# untitled.net
KiCad netlist of a schematic drawn in EAGLE
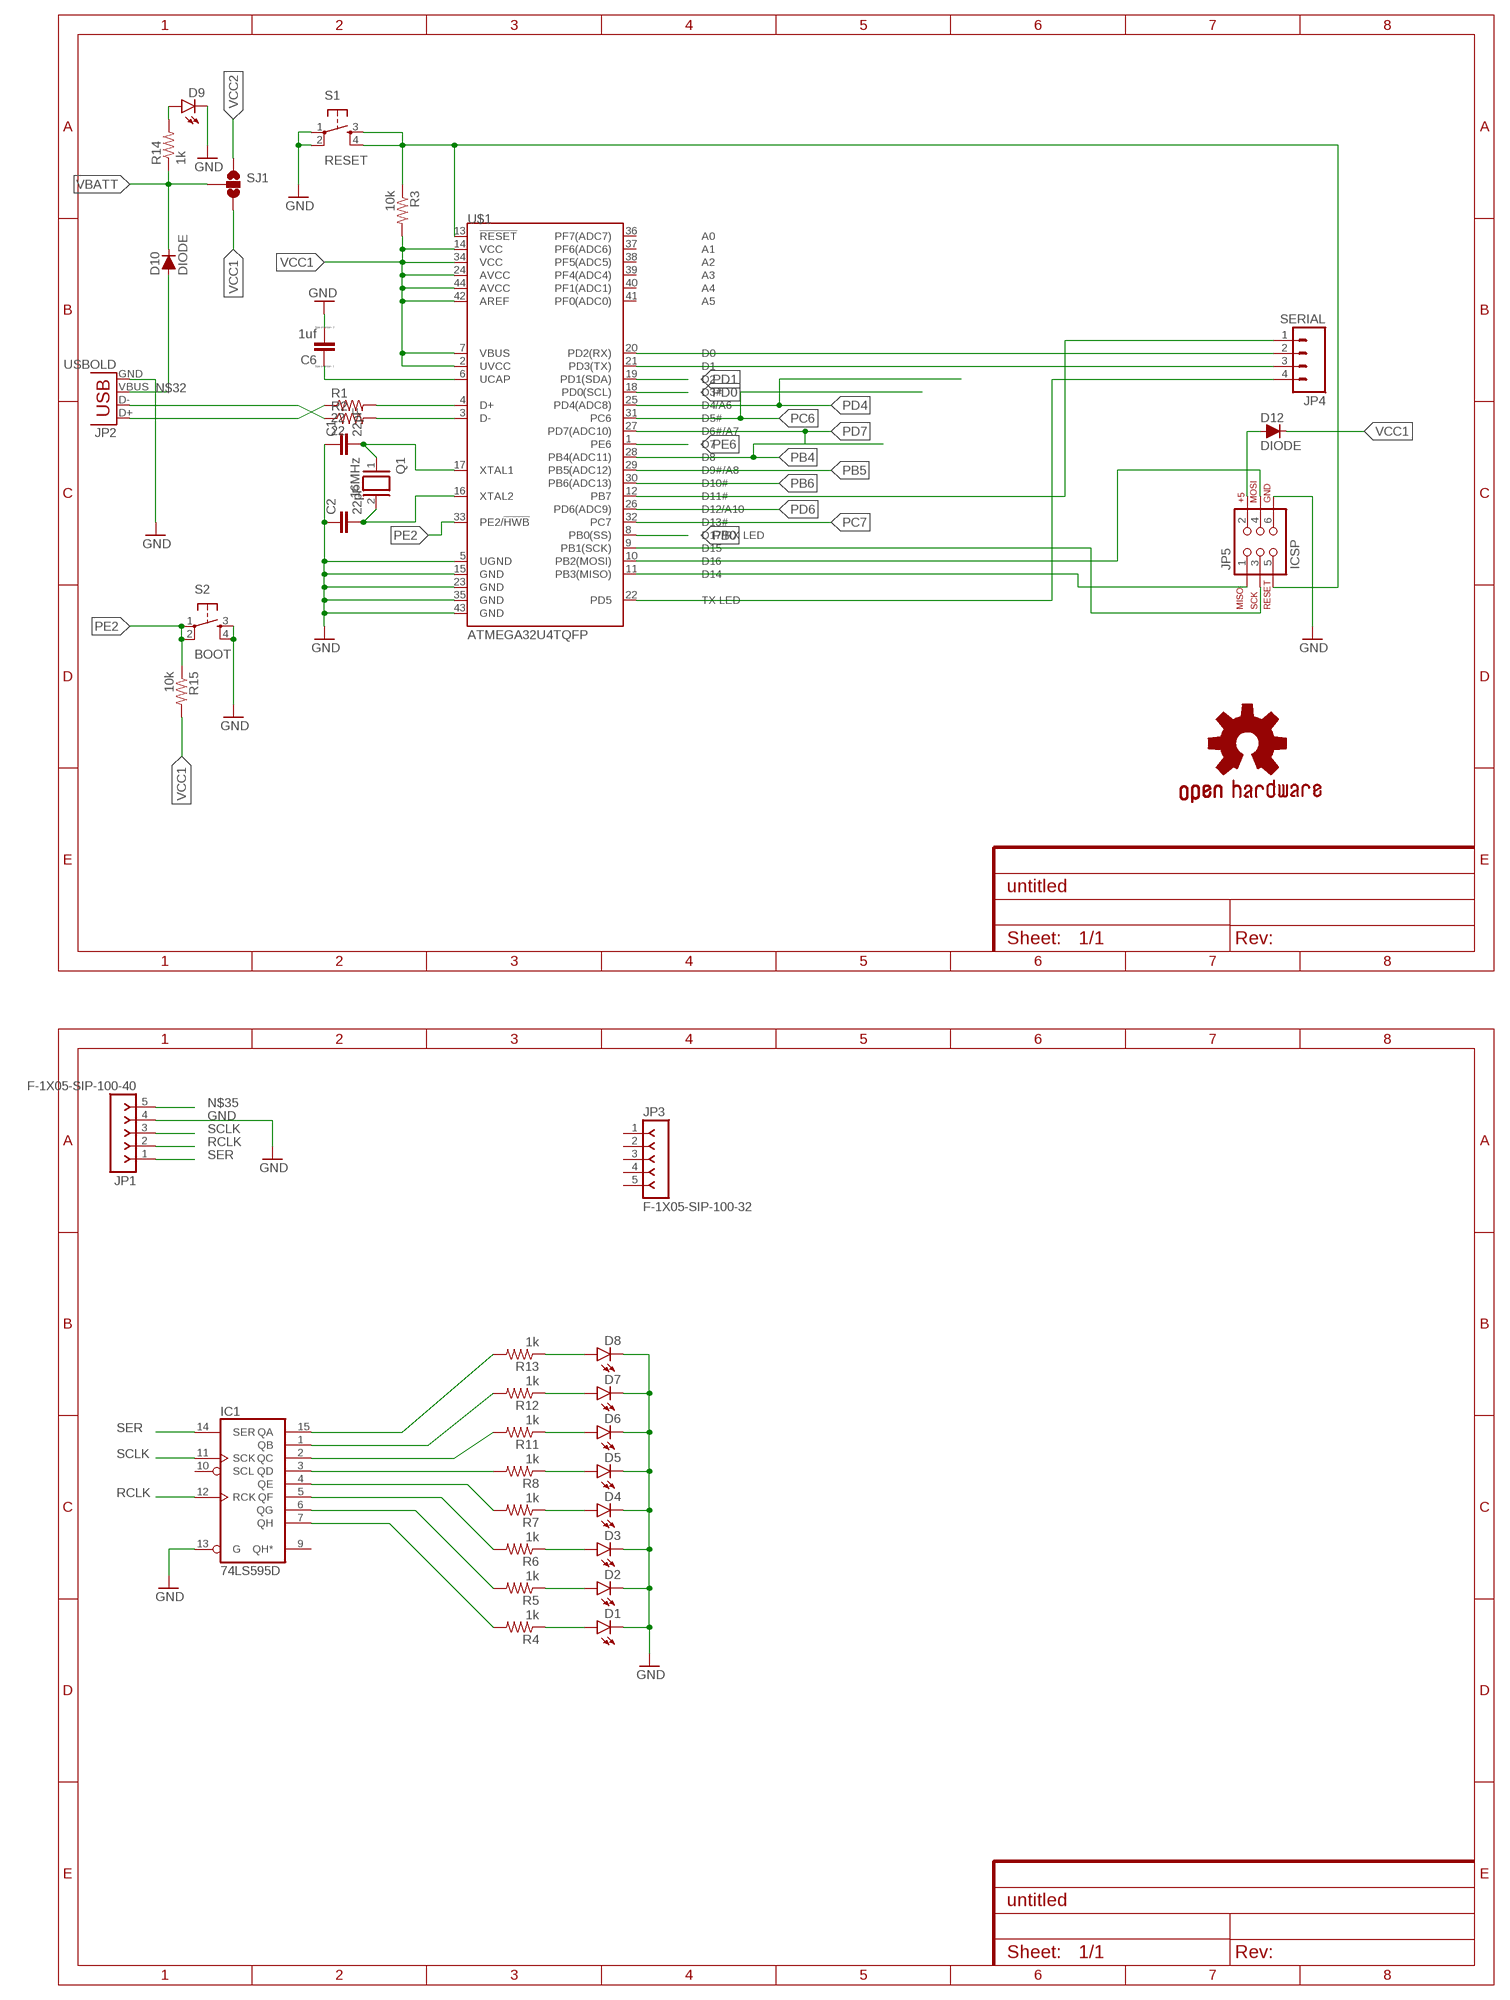
[diagram p0: schematic, sheet 1]

(export (version "E")
  (design (tool "Eeschema 10.0.6"))
  (components
    (comp (ref "C1")
      (value "22pF")
      (footprint "eagle-import:0603-CAP")
      (libsource (lib "eagle-import") (part "CAP0603-CAP"))
    )
    (comp (ref "C2")
      (value "22pF")
      (footprint "eagle-import:0603-CAP")
      (libsource (lib "eagle-import") (part "CAP0603-CAP"))
    )
    (comp (ref "C6")
      (value "1uf")
      (footprint "eagle-import:C0603")
      (libsource (lib "eagle-import") (part "CC0603"))
    )
    (comp (ref "D1")
      (value "LED1206")
      (footprint "eagle-import:LED-1206")
      (libsource (lib "eagle-import") (part "LED1206"))
    )
    (comp (ref "D2")
      (value "LED1206")
      (footprint "eagle-import:LED-1206")
      (libsource (lib "eagle-import") (part "LED1206"))
    )
    (comp (ref "D3")
      (value "LED1206")
      (footprint "eagle-import:LED-1206")
      (libsource (lib "eagle-import") (part "LED1206"))
    )
    (comp (ref "D4")
      (value "LED1206")
      (footprint "eagle-import:LED-1206")
      (libsource (lib "eagle-import") (part "LED1206"))
    )
    (comp (ref "D5")
      (value "LED1206")
      (footprint "eagle-import:LED-1206")
      (libsource (lib "eagle-import") (part "LED1206"))
    )
    (comp (ref "D6")
      (value "LED1206")
      (footprint "eagle-import:LED-1206")
      (libsource (lib "eagle-import") (part "LED1206"))
    )
    (comp (ref "D7")
      (value "LED1206")
      (footprint "eagle-import:LED-1206")
      (libsource (lib "eagle-import") (part "LED1206"))
    )
    (comp (ref "D8")
      (value "LED1206")
      (footprint "eagle-import:LED-1206")
      (libsource (lib "eagle-import") (part "LED1206"))
    )
    (comp (ref "D9")
      (value "LED1206")
      (footprint "eagle-import:LED-1206")
      (libsource (lib "eagle-import") (part "LED1206"))
    )
    (comp (ref "D10")
      (value "DIODE")
      (footprint "eagle-import:1206")
      (libsource (lib "eagle-import") (part "DIODE"))
    )
    (comp (ref "D12")
      (value "DIODE")
      (footprint "eagle-import:1206")
      (libsource (lib "eagle-import") (part "DIODE"))
    )
    (comp (ref "GOLD_ORB_SM1")
      (value "OSHWLOGO_GOLD_ORB_LG")
      (footprint "eagle-import:OSHW0")
      (libsource (lib "eagle-import") (part "OSHWLOGO_GOLD_ORB_LG"))
    )
    (comp (ref "IC1")
      (value "74LS595D")
      (footprint "eagle-import:SO16")
      (libsource (lib "eagle-import") (part "74595DLS"))
    )
    (comp (ref "JP1")
      (value "F-1X05-SIP-100-40")
      (footprint "eagle-import:SIP-100-05-40")
      (libsource (lib "eagle-import") (part "F-1X05-SIP-100-40"))
    )
    (comp (ref "JP2")
      (value "USBOLD")
      (footprint "eagle-import:USB-MINIB-OLD")
      (libsource (lib "eagle-import") (part "USBOLD"))
    )
    (comp (ref "JP3")
      (value "F-1X05-SIP-100-32")
      (footprint "eagle-import:SIP-100-05-32")
      (libsource (lib "eagle-import") (part "F-1X05-SIP-100-32"))
    )
    (comp (ref "JP4")
      (value "SERIAL")
      (footprint "eagle-import:1X04_LOCK_LONGPADS")
      (libsource (lib "eagle-import") (part "M04LOCK_LONGPADS"))
    )
    (comp (ref "JP5")
      (value "ICSP")
      (footprint "eagle-import:2X3")
      (libsource (lib "eagle-import") (part "AVR_SPI_PRG_6PTH"))
    )
    (comp (ref "Q1")
      (value "16MHz")
      (footprint "eagle-import:QS")
      (libsource (lib "eagle-import") (part "XTAL/S"))
    )
    (comp (ref "R1")
      (value "22")
      (footprint "eagle-import:0603-RES")
      (libsource (lib "eagle-import") (part "RESISTOR0603-RES"))
    )
    (comp (ref "R2")
      (value "22")
      (footprint "eagle-import:0603-RES")
      (libsource (lib "eagle-import") (part "RESISTOR0603-RES"))
    )
    (comp (ref "R3")
      (value "10k")
      (footprint "eagle-import:0603-RES")
      (libsource (lib "eagle-import") (part "RESISTOR0603-RES"))
    )
    (comp (ref "R4")
      (value "1k")
      (footprint "eagle-import:0603-RES")
      (libsource (lib "eagle-import") (part "RESISTOR0603-RES"))
    )
    (comp (ref "R5")
      (value "1k")
      (footprint "eagle-import:0603-RES")
      (libsource (lib "eagle-import") (part "RESISTOR0603-RES"))
    )
    (comp (ref "R6")
      (value "1k")
      (footprint "eagle-import:0603-RES")
      (libsource (lib "eagle-import") (part "RESISTOR0603-RES"))
    )
    (comp (ref "R7")
      (value "1k")
      (footprint "eagle-import:0603-RES")
      (libsource (lib "eagle-import") (part "RESISTOR0603-RES"))
    )
    (comp (ref "R8")
      (value "1k")
      (footprint "eagle-import:0603-RES")
      (libsource (lib "eagle-import") (part "RESISTOR0603-RES"))
    )
    (comp (ref "R11")
      (value "1k")
      (footprint "eagle-import:0603-RES")
      (libsource (lib "eagle-import") (part "RESISTOR0603-RES"))
    )
    (comp (ref "R12")
      (value "1k")
      (footprint "eagle-import:0603-RES")
      (libsource (lib "eagle-import") (part "RESISTOR0603-RES"))
    )
    (comp (ref "R13")
      (value "1k")
      (footprint "eagle-import:0603-RES")
      (libsource (lib "eagle-import") (part "RESISTOR0603-RES"))
    )
    (comp (ref "R14")
      (value "1k")
      (footprint "eagle-import:1206")
      (libsource (lib "eagle-import") (part "RESISTOR1206"))
    )
    (comp (ref "R15")
      (value "10k")
      (footprint "eagle-import:0603-RES")
      (libsource (lib "eagle-import") (part "RESISTOR0603-RES"))
    )
    (comp (ref "S1")
      (value "RESET")
      (footprint "eagle-import:TACTILE-SWITCH-SMD")
      (libsource (lib "eagle-import") (part "TAC_SWITCHSMD"))
    )
    (comp (ref "S2")
      (value "BOOT")
      (footprint "eagle-import:TACTILE-SWITCH-SMD")
      (libsource (lib "eagle-import") (part "TAC_SWITCHSMD"))
    )
    (comp (ref "SJ1")
      (value "SOLDERJUMPER_2WAYPASTE2&3")
      (footprint "eagle-import:SJ_3_PASTE2&3")
      (libsource (lib "eagle-import") (part "SOLDERJUMPER_2WAYPASTE2&3"))
    )
    (comp (ref "U$1")
      (value "ATMEGA32U4TQFP")
      (footprint "eagle-import:SPARKFUN-DIGITALIC_TQFP44")
      (libsource (lib "eagle-import") (part "ATMEGA32U4TQFP"))
    )
  )
  (nets
    (net (code "1") (name "/N$32") (class "Default")
      (node (ref "D10") (pin "P$1") (pinfunction "A_P$1") (pintype "passive"))
      (node (ref "JP2") (pin "VBUS") (pinfunction "VBUS_VBUS") (pintype "bidirectional"))
    )
    (net (code "2") (name "/N$35") (class "Default")
      (node (ref "JP1") (pin "5") (pinfunction "5_5") (pintype "passive"))
    )
    (net (code "3") (name "/RCLK") (class "Default")
      (node (ref "IC1") (pin "12") (pinfunction "RCK_12") (pintype "input"))
      (node (ref "JP1") (pin "2") (pinfunction "2_2") (pintype "passive"))
    )
    (net (code "4") (name "/SCLK") (class "Default")
      (node (ref "IC1") (pin "11") (pinfunction "SCK_11") (pintype "input"))
      (node (ref "JP1") (pin "3") (pinfunction "3_3") (pintype "passive"))
    )
    (net (code "5") (name "/SER") (class "Default")
      (node (ref "IC1") (pin "14") (pinfunction "SER_14") (pintype "input"))
      (node (ref "JP1") (pin "1") (pinfunction "1_1") (pintype "passive"))
    )
    (net (code "6") (name "GND") (class "Default")
      (node (ref "C1") (pin "1") (pinfunction "1_1") (pintype "passive"))
      (node (ref "C2") (pin "1") (pinfunction "1_1") (pintype "passive"))
      (node (ref "C6") (pin "2") (pinfunction "2_2") (pintype "passive"))
      (node (ref "D1") (pin "C") (pinfunction "C_C") (pintype "passive"))
      (node (ref "D2") (pin "C") (pinfunction "C_C") (pintype "passive"))
      (node (ref "D3") (pin "C") (pinfunction "C_C") (pintype "passive"))
      (node (ref "D4") (pin "C") (pinfunction "C_C") (pintype "passive"))
      (node (ref "D5") (pin "C") (pinfunction "C_C") (pintype "passive"))
      (node (ref "D6") (pin "C") (pinfunction "C_C") (pintype "passive"))
      (node (ref "D7") (pin "C") (pinfunction "C_C") (pintype "passive"))
      (node (ref "D8") (pin "C") (pinfunction "C_C") (pintype "passive"))
      (node (ref "D9") (pin "C") (pinfunction "C_C") (pintype "passive"))
      (node (ref "IC1") (pin "13") (pinfunction "G_13") (pintype "input"))
      (node (ref "JP1") (pin "4") (pinfunction "4_4") (pintype "passive"))
      (node (ref "JP2") (pin "GND") (pinfunction "GND_GND") (pintype "bidirectional"))
      (node (ref "JP5") (pin "6") (pinfunction "6_6") (pintype "passive"))
      (node (ref "S1") (pin "1") (pinfunction "1_1") (pintype "passive"))
      (node (ref "S1") (pin "2") (pinfunction "2_2") (pintype "passive"))
      (node (ref "S2") (pin "3") (pinfunction "3_3") (pintype "passive"))
      (node (ref "S2") (pin "4") (pinfunction "4_4") (pintype "passive"))
      (node (ref "U$1") (pin "15") (pinfunction "GND_15") (pintype "bidirectional"))
      (node (ref "U$1") (pin "23") (pinfunction "GND_23") (pintype "bidirectional"))
      (node (ref "U$1") (pin "35") (pinfunction "GND_35") (pintype "bidirectional"))
      (node (ref "U$1") (pin "43") (pinfunction "GND_43") (pintype "bidirectional"))
      (node (ref "U$1") (pin "5") (pinfunction "UGND_5") (pintype "bidirectional"))
    )
    (net (code "7") (name "Net-(D1-PadA)") (class "Default")
      (node (ref "D1") (pin "A") (pinfunction "A_A") (pintype "passive"))
      (node (ref "R4") (pin "1") (pinfunction "1_1") (pintype "passive"))
    )
    (net (code "8") (name "Net-(D2-PadA)") (class "Default")
      (node (ref "D2") (pin "A") (pinfunction "A_A") (pintype "passive"))
      (node (ref "R5") (pin "1") (pinfunction "1_1") (pintype "passive"))
    )
    (net (code "9") (name "Net-(D3-PadA)") (class "Default")
      (node (ref "D3") (pin "A") (pinfunction "A_A") (pintype "passive"))
      (node (ref "R6") (pin "1") (pinfunction "1_1") (pintype "passive"))
    )
    (net (code "10") (name "Net-(D4-PadA)") (class "Default")
      (node (ref "D4") (pin "A") (pinfunction "A_A") (pintype "passive"))
      (node (ref "R7") (pin "1") (pinfunction "1_1") (pintype "passive"))
    )
    (net (code "11") (name "Net-(D5-PadA)") (class "Default")
      (node (ref "D5") (pin "A") (pinfunction "A_A") (pintype "passive"))
      (node (ref "R8") (pin "1") (pinfunction "1_1") (pintype "passive"))
    )
    (net (code "12") (name "Net-(D6-PadA)") (class "Default")
      (node (ref "D6") (pin "A") (pinfunction "A_A") (pintype "passive"))
      (node (ref "R11") (pin "1") (pinfunction "1_1") (pintype "passive"))
    )
    (net (code "13") (name "Net-(D7-PadA)") (class "Default")
      (node (ref "D7") (pin "A") (pinfunction "A_A") (pintype "passive"))
      (node (ref "R12") (pin "1") (pinfunction "1_1") (pintype "passive"))
    )
    (net (code "14") (name "Net-(D8-PadA)") (class "Default")
      (node (ref "D8") (pin "A") (pinfunction "A_A") (pintype "passive"))
      (node (ref "R13") (pin "1") (pinfunction "1_1") (pintype "passive"))
    )
    (net (code "15") (name "Net-(D9-PadA)") (class "Default")
      (node (ref "D9") (pin "A") (pinfunction "A_A") (pintype "passive"))
      (node (ref "R14") (pin "2") (pinfunction "2_2") (pintype "passive"))
    )
    (net (code "16") (name "Net-(D12-A)") (class "Default")
      (node (ref "D12") (pin "P$1") (pinfunction "A_P$1") (pintype "passive"))
      (node (ref "JP5") (pin "2") (pinfunction "2_2") (pintype "passive"))
    )
    (net (code "17") (name "Net-(IC1A-QA)") (class "Default")
      (node (ref "IC1") (pin "15") (pinfunction "QA_15") (pintype "tri_state"))
      (node (ref "R13") (pin "2") (pinfunction "2_2") (pintype "passive"))
    )
    (net (code "18") (name "Net-(IC1A-QB)") (class "Default")
      (node (ref "IC1") (pin "1") (pinfunction "QB_1") (pintype "tri_state"))
      (node (ref "R12") (pin "2") (pinfunction "2_2") (pintype "passive"))
    )
    (net (code "19") (name "Net-(IC1A-QC)") (class "Default")
      (node (ref "IC1") (pin "2") (pinfunction "QC_2") (pintype "tri_state"))
      (node (ref "R11") (pin "2") (pinfunction "2_2") (pintype "passive"))
    )
    (net (code "20") (name "Net-(IC1A-QD)") (class "Default")
      (node (ref "IC1") (pin "3") (pinfunction "QD_3") (pintype "tri_state"))
      (node (ref "R8") (pin "2") (pinfunction "2_2") (pintype "passive"))
    )
    (net (code "21") (name "Net-(IC1A-QE)") (class "Default")
      (node (ref "IC1") (pin "4") (pinfunction "QE_4") (pintype "tri_state"))
      (node (ref "R7") (pin "2") (pinfunction "2_2") (pintype "passive"))
    )
    (net (code "22") (name "Net-(IC1A-QF)") (class "Default")
      (node (ref "IC1") (pin "5") (pinfunction "QF_5") (pintype "tri_state"))
      (node (ref "R6") (pin "2") (pinfunction "2_2") (pintype "passive"))
    )
    (net (code "23") (name "Net-(IC1A-QG)") (class "Default")
      (node (ref "IC1") (pin "6") (pinfunction "QG_6") (pintype "tri_state"))
      (node (ref "R5") (pin "2") (pinfunction "2_2") (pintype "passive"))
    )
    (net (code "24") (name "Net-(IC1A-QH)") (class "Default")
      (node (ref "IC1") (pin "7") (pinfunction "QH_7") (pintype "tri_state"))
      (node (ref "R4") (pin "2") (pinfunction "2_2") (pintype "passive"))
    )
    (net (code "25") (name "Net-(JP2-PadD+)") (class "Default")
      (node (ref "JP2") (pin "D+") (pinfunction "D+_D+") (pintype "bidirectional"))
      (node (ref "R1") (pin "1") (pinfunction "1_1") (pintype "passive"))
    )
    (net (code "26") (name "Net-(JP2-PadD-)") (class "Default")
      (node (ref "JP2") (pin "D-") (pinfunction "D-_D-") (pintype "bidirectional"))
      (node (ref "R2") (pin "1") (pinfunction "1_1") (pintype "passive"))
    )
    (net (code "27") (name "Net-(U$1-D+)") (class "Default")
      (node (ref "R1") (pin "2") (pinfunction "2_2") (pintype "passive"))
      (node (ref "U$1") (pin "4") (pinfunction "D+_4") (pintype "bidirectional"))
    )
    (net (code "28") (name "Net-(U$1-D-)") (class "Default")
      (node (ref "R2") (pin "2") (pinfunction "2_2") (pintype "passive"))
      (node (ref "U$1") (pin "3") (pinfunction "D-_3") (pintype "bidirectional"))
    )
    (net (code "29") (name "Net-(U$1-PB1(SCK))") (class "Default")
      (node (ref "JP5") (pin "3") (pinfunction "3_3") (pintype "passive"))
      (node (ref "U$1") (pin "9") (pinfunction "PB1(SCK)_9") (pintype "bidirectional"))
    )
    (net (code "30") (name "Net-(U$1-PB2(MOSI))") (class "Default")
      (node (ref "JP5") (pin "4") (pinfunction "4_4") (pintype "passive"))
      (node (ref "U$1") (pin "10") (pinfunction "PB2(MOSI)_10") (pintype "bidirectional"))
    )
    (net (code "31") (name "Net-(U$1-PB3(MISO))") (class "Default")
      (node (ref "JP5") (pin "1") (pinfunction "1_1") (pintype "passive"))
      (node (ref "U$1") (pin "11") (pinfunction "PB3(MISO)_11") (pintype "bidirectional"))
    )
    (net (code "32") (name "Net-(U$1-PB7)") (class "Default")
      (node (ref "JP4") (pin "1") (pinfunction "1_1") (pintype "passive"))
      (node (ref "U$1") (pin "12") (pinfunction "PB7_12") (pintype "bidirectional"))
    )
    (net (code "33") (name "Net-(U$1-PD2(RX))") (class "Default")
      (node (ref "JP4") (pin "2") (pinfunction "2_2") (pintype "passive"))
      (node (ref "U$1") (pin "20") (pinfunction "PD2(RX)_20") (pintype "bidirectional"))
    )
    (net (code "34") (name "Net-(U$1-PD3(TX))") (class "Default")
      (node (ref "JP4") (pin "3") (pinfunction "3_3") (pintype "passive"))
      (node (ref "U$1") (pin "21") (pinfunction "PD3(TX)_21") (pintype "bidirectional"))
    )
    (net (code "35") (name "Net-(U$1-PD5)") (class "Default")
      (node (ref "JP4") (pin "4") (pinfunction "4_4") (pintype "passive"))
      (node (ref "U$1") (pin "22") (pinfunction "PD5_22") (pintype "bidirectional"))
    )
    (net (code "36") (name "Net-(U$1-UCAP)") (class "Default")
      (node (ref "C6") (pin "1") (pinfunction "1_1") (pintype "passive"))
      (node (ref "U$1") (pin "6") (pinfunction "UCAP_6") (pintype "bidirectional"))
    )
    (net (code "37") (name "Net-(U$1-XTAL1)") (class "Default")
      (node (ref "C1") (pin "2") (pinfunction "2_2") (pintype "passive"))
      (node (ref "Q1") (pin "1") (pinfunction "1_1") (pintype "passive"))
      (node (ref "U$1") (pin "17") (pinfunction "XTAL1_17") (pintype "bidirectional"))
    )
    (net (code "38") (name "Net-(U$1-XTAL2)") (class "Default")
      (node (ref "C2") (pin "2") (pinfunction "2_2") (pintype "passive"))
      (node (ref "Q1") (pin "2") (pinfunction "2_2") (pintype "passive"))
      (node (ref "U$1") (pin "16") (pinfunction "XTAL2_16") (pintype "bidirectional"))
    )
    (net (code "39") (name "Net-(U$1-~{RESET})") (class "Default")
      (node (ref "JP5") (pin "5") (pinfunction "5_5") (pintype "passive"))
      (node (ref "R3") (pin "1") (pinfunction "1_1") (pintype "passive"))
      (node (ref "S1") (pin "3") (pinfunction "3_3") (pintype "passive"))
      (node (ref "S1") (pin "4") (pinfunction "4_4") (pintype "passive"))
      (node (ref "U$1") (pin "13") (pinfunction "~{RESET}_13") (pintype "bidirectional"))
    )
    (net (code "40") (name "PB0") (class "Default")
      (node (ref "U$1") (pin "8") (pinfunction "PB0(SS)_8") (pintype "bidirectional"))
    )
    (net (code "41") (name "PB4") (class "Default")
      (node (ref "U$1") (pin "28") (pinfunction "PB4(ADC11)_28") (pintype "bidirectional"))
    )
    (net (code "42") (name "PB5") (class "Default")
      (node (ref "U$1") (pin "29") (pinfunction "PB5(ADC12)_29") (pintype "bidirectional"))
    )
    (net (code "43") (name "PB6") (class "Default")
      (node (ref "U$1") (pin "30") (pinfunction "PB6(ADC13)_30") (pintype "bidirectional"))
    )
    (net (code "44") (name "PC6") (class "Default")
      (node (ref "U$1") (pin "31") (pinfunction "PC6_31") (pintype "bidirectional"))
    )
    (net (code "45") (name "PC7") (class "Default")
      (node (ref "U$1") (pin "32") (pinfunction "PC7_32") (pintype "bidirectional"))
    )
    (net (code "46") (name "PD0") (class "Default")
      (node (ref "U$1") (pin "18") (pinfunction "PD0(SCL)_18") (pintype "bidirectional"))
    )
    (net (code "47") (name "PD1") (class "Default")
      (node (ref "U$1") (pin "19") (pinfunction "PD1(SDA)_19") (pintype "bidirectional"))
    )
    (net (code "48") (name "PD4") (class "Default")
      (node (ref "U$1") (pin "25") (pinfunction "PD4(ADC8)_25") (pintype "bidirectional"))
    )
    (net (code "49") (name "PD6") (class "Default")
      (node (ref "U$1") (pin "26") (pinfunction "PD6(ADC9)_26") (pintype "bidirectional"))
    )
    (net (code "50") (name "PD7") (class "Default")
      (node (ref "U$1") (pin "27") (pinfunction "PD7(ADC10)_27") (pintype "bidirectional"))
    )
    (net (code "51") (name "PE2") (class "Default")
      (node (ref "R15") (pin "1") (pinfunction "1_1") (pintype "passive"))
      (node (ref "S2") (pin "1") (pinfunction "1_1") (pintype "passive"))
      (node (ref "S2") (pin "2") (pinfunction "2_2") (pintype "passive"))
      (node (ref "U$1") (pin "33") (pinfunction "PE2/~{HWB}_33") (pintype "bidirectional"))
    )
    (net (code "52") (name "PE6") (class "Default")
      (node (ref "U$1") (pin "1") (pinfunction "PE6_1") (pintype "bidirectional"))
    )
    (net (code "53") (name "VBATT") (class "Default")
      (node (ref "D10") (pin "P$2") (pinfunction "C_P$2") (pintype "passive"))
      (node (ref "R14") (pin "1") (pinfunction "1_1") (pintype "passive"))
      (node (ref "SJ1") (pin "2") (pinfunction "2_2") (pintype "passive"))
    )
    (net (code "54") (name "VCC1") (class "Default")
      (node (ref "D12") (pin "P$2") (pinfunction "C_P$2") (pintype "passive"))
      (node (ref "R15") (pin "2") (pinfunction "2_2") (pintype "passive"))
      (node (ref "R3") (pin "2") (pinfunction "2_2") (pintype "passive"))
      (node (ref "SJ1") (pin "3") (pinfunction "3_3") (pintype "passive"))
      (node (ref "U$1") (pin "14") (pinfunction "VCC_14") (pintype "bidirectional"))
      (node (ref "U$1") (pin "2") (pinfunction "UVCC_2") (pintype "bidirectional"))
      (node (ref "U$1") (pin "24") (pinfunction "AVCC_24") (pintype "bidirectional"))
      (node (ref "U$1") (pin "34") (pinfunction "VCC_34") (pintype "bidirectional"))
      (node (ref "U$1") (pin "42") (pinfunction "AREF_42") (pintype "bidirectional"))
      (node (ref "U$1") (pin "44") (pinfunction "AVCC_44") (pintype "bidirectional"))
      (node (ref "U$1") (pin "7") (pinfunction "VBUS_7") (pintype "bidirectional"))
    )
    (net (code "55") (name "VCC2") (class "Default")
      (node (ref "SJ1") (pin "1") (pinfunction "1_1") (pintype "passive"))
    )
    (net (code "56") (name "unconnected-(IC1A-QH*-Pad9)") (class "Default")
      (node (ref "IC1") (pin "9") (pinfunction "QH*_9") (pintype "tri_state"))
    )
    (net (code "57") (name "unconnected-(IC1A-SCL-Pad10)") (class "Default")
      (node (ref "IC1") (pin "10") (pinfunction "SCL_10") (pintype "input"))
    )
    (net (code "58") (name "unconnected-(JP3-Pad1)") (class "Default")
      (node (ref "JP3") (pin "1") (pinfunction "1_1") (pintype "passive"))
    )
    (net (code "59") (name "unconnected-(JP3-Pad2)") (class "Default")
      (node (ref "JP3") (pin "2") (pinfunction "2_2") (pintype "passive"))
    )
    (net (code "60") (name "unconnected-(JP3-Pad3)") (class "Default")
      (node (ref "JP3") (pin "3") (pinfunction "3_3") (pintype "passive"))
    )
    (net (code "61") (name "unconnected-(JP3-Pad4)") (class "Default")
      (node (ref "JP3") (pin "4") (pinfunction "4_4") (pintype "passive"))
    )
    (net (code "62") (name "unconnected-(JP3-Pad5)") (class "Default")
      (node (ref "JP3") (pin "5") (pinfunction "5_5") (pintype "passive"))
    )
    (net (code "63") (name "unconnected-(U$1-PF0(ADC0)-Pad41)") (class "Default")
      (node (ref "U$1") (pin "41") (pinfunction "PF0(ADC0)_41") (pintype "bidirectional"))
    )
    (net (code "64") (name "unconnected-(U$1-PF1(ADC1)-Pad40)") (class "Default")
      (node (ref "U$1") (pin "40") (pinfunction "PF1(ADC1)_40") (pintype "bidirectional"))
    )
    (net (code "65") (name "unconnected-(U$1-PF4(ADC4)-Pad39)") (class "Default")
      (node (ref "U$1") (pin "39") (pinfunction "PF4(ADC4)_39") (pintype "bidirectional"))
    )
    (net (code "66") (name "unconnected-(U$1-PF5(ADC5)-Pad38)") (class "Default")
      (node (ref "U$1") (pin "38") (pinfunction "PF5(ADC5)_38") (pintype "bidirectional"))
    )
    (net (code "67") (name "unconnected-(U$1-PF6(ADC6)-Pad37)") (class "Default")
      (node (ref "U$1") (pin "37") (pinfunction "PF6(ADC6)_37") (pintype "bidirectional"))
    )
    (net (code "68") (name "unconnected-(U$1-PF7(ADC7)-Pad36)") (class "Default")
      (node (ref "U$1") (pin "36") (pinfunction "PF7(ADC7)_36") (pintype "bidirectional"))
    )
  )
)
